# Infinity_Mirror_002.net
KiCad netlist of a schematic drawn in EAGLE
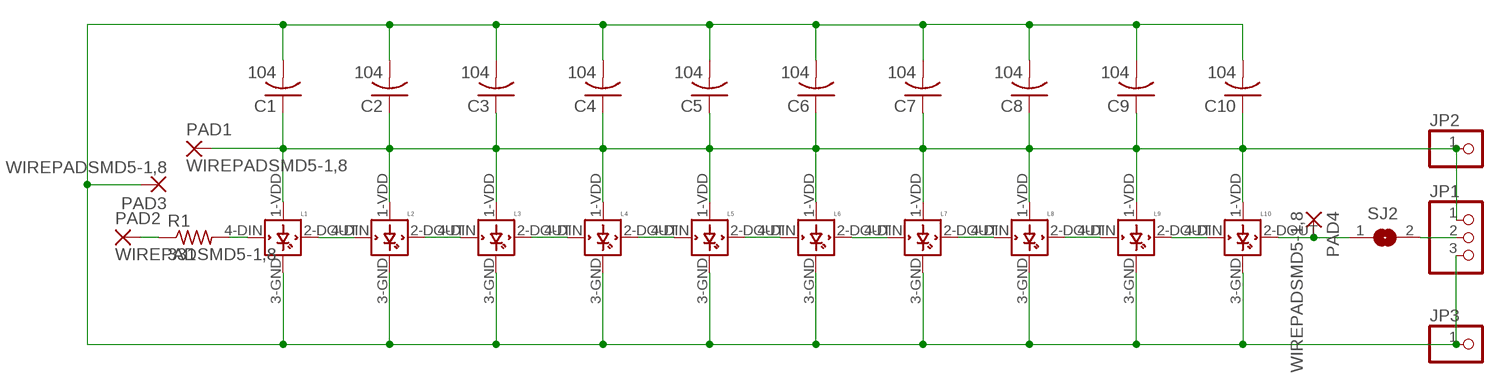
[diagram p0: schematic, sheet 1]

(export (version "E")
  (design (tool "Eeschema 10.0.6"))
  (components
    (comp (ref "C1")
      (value "104")
      (footprint "eagle-import:C1206")
      (libsource (lib "eagle-import") (part "C-USC1206"))
    )
    (comp (ref "C2")
      (value "104")
      (footprint "eagle-import:C1206")
      (libsource (lib "eagle-import") (part "C-USC1206"))
    )
    (comp (ref "C3")
      (value "104")
      (footprint "eagle-import:C1206")
      (libsource (lib "eagle-import") (part "C-USC1206"))
    )
    (comp (ref "C4")
      (value "104")
      (footprint "eagle-import:C1206")
      (libsource (lib "eagle-import") (part "C-USC1206"))
    )
    (comp (ref "C5")
      (value "104")
      (footprint "eagle-import:C1206")
      (libsource (lib "eagle-import") (part "C-USC1206"))
    )
    (comp (ref "C6")
      (value "104")
      (footprint "eagle-import:C1206")
      (libsource (lib "eagle-import") (part "C-USC1206"))
    )
    (comp (ref "C7")
      (value "104")
      (footprint "eagle-import:C1206")
      (libsource (lib "eagle-import") (part "C-USC1206"))
    )
    (comp (ref "C8")
      (value "104")
      (footprint "eagle-import:C1206")
      (libsource (lib "eagle-import") (part "C-USC1206"))
    )
    (comp (ref "C9")
      (value "104")
      (footprint "eagle-import:C1206")
      (libsource (lib "eagle-import") (part "C-USC1206"))
    )
    (comp (ref "C10")
      (value "104")
      (footprint "eagle-import:C1206")
      (libsource (lib "eagle-import") (part "C-USC1206"))
    )
    (comp (ref "JP1")
      (value "PINHD-1X3CB")
      (footprint "eagle-import:1X03-CLEANBIG")
      (libsource (lib "eagle-import") (part "PINHD-1X3CB"))
    )
    (comp (ref "JP2")
      (value "PINHD-1X1CB")
      (footprint "eagle-import:1X01-CLEANBIG")
      (libsource (lib "eagle-import") (part "PINHD-1X1CB"))
    )
    (comp (ref "JP3")
      (value "PINHD-1X1CB")
      (footprint "eagle-import:1X01-CLEANBIG")
      (libsource (lib "eagle-import") (part "PINHD-1X1CB"))
    )
    (comp (ref "L1")
      (value "WS2812B")
      (footprint "eagle-import:WS2812B")
      (libsource (lib "eagle-import") (part "WS2812B"))
    )
    (comp (ref "L2")
      (value "WS2812B")
      (footprint "eagle-import:WS2812B")
      (libsource (lib "eagle-import") (part "WS2812B"))
    )
    (comp (ref "L3")
      (value "WS2812B")
      (footprint "eagle-import:WS2812B")
      (libsource (lib "eagle-import") (part "WS2812B"))
    )
    (comp (ref "L4")
      (value "WS2812B")
      (footprint "eagle-import:WS2812B")
      (libsource (lib "eagle-import") (part "WS2812B"))
    )
    (comp (ref "L5")
      (value "WS2812B")
      (footprint "eagle-import:WS2812B")
      (libsource (lib "eagle-import") (part "WS2812B"))
    )
    (comp (ref "L6")
      (value "WS2812B")
      (footprint "eagle-import:WS2812B")
      (libsource (lib "eagle-import") (part "WS2812B"))
    )
    (comp (ref "L7")
      (value "WS2812B")
      (footprint "eagle-import:WS2812B")
      (libsource (lib "eagle-import") (part "WS2812B"))
    )
    (comp (ref "L8")
      (value "WS2812B")
      (footprint "eagle-import:WS2812B")
      (libsource (lib "eagle-import") (part "WS2812B"))
    )
    (comp (ref "L9")
      (value "WS2812B")
      (footprint "eagle-import:WS2812B")
      (libsource (lib "eagle-import") (part "WS2812B"))
    )
    (comp (ref "L10")
      (value "WS2812B")
      (footprint "eagle-import:WS2812B")
      (libsource (lib "eagle-import") (part "WS2812B"))
    )
    (comp (ref "PAD1")
      (value "WIREPADSMD5-1,8")
      (footprint "eagle-import:5-1,8")
      (libsource (lib "eagle-import") (part "WIREPADSMD5-1,8"))
    )
    (comp (ref "PAD2")
      (value "WIREPADSMD5-1,8")
      (footprint "eagle-import:5-1,8")
      (libsource (lib "eagle-import") (part "WIREPADSMD5-1,8"))
    )
    (comp (ref "PAD3")
      (value "WIREPADSMD5-1,8")
      (footprint "eagle-import:5-1,8")
      (libsource (lib "eagle-import") (part "WIREPADSMD5-1,8"))
    )
    (comp (ref "PAD4")
      (value "WIREPADSMD5-1,8")
      (footprint "eagle-import:5-1,8")
      (libsource (lib "eagle-import") (part "WIREPADSMD5-1,8"))
    )
    (comp (ref "R1")
      (value "331")
      (footprint "eagle-import:R1206")
      (libsource (lib "eagle-import") (part "R-US_R1206"))
    )
    (comp (ref "SJ2") (value "SJ") (footprint "eagle-import:SJ") (libsource (lib "eagle-import") (part "SJ")))
  )
  (nets
    (net (code "1") (name "Net-(JP1-Pad2)") (class "Default")
      (node (ref "JP1") (pin "2") (pinfunction "2_2") (pintype "passive"))
      (node (ref "SJ2") (pin "2") (pinfunction "2_2") (pintype "passive"))
    )
    (net (code "2") (name "Net-(L1-DIN)") (class "Default")
      (node (ref "L1") (pin "4-DIN") (pinfunction "DIN_4-DIN") (pintype "input"))
      (node (ref "R1") (pin "2") (pinfunction "2_2") (pintype "passive"))
    )
    (net (code "3") (name "Net-(L1-DOUT)") (class "Default")
      (node (ref "L1") (pin "2-DOUT") (pinfunction "DOUT_2-DOUT") (pintype "output"))
      (node (ref "L2") (pin "4-DIN") (pinfunction "DIN_4-DIN") (pintype "input"))
    )
    (net (code "4") (name "Net-(L1-GND)") (class "Default")
      (node (ref "C1") (pin "2") (pinfunction "2_2") (pintype "passive"))
      (node (ref "C10") (pin "2") (pinfunction "2_2") (pintype "passive"))
      (node (ref "C2") (pin "2") (pinfunction "2_2") (pintype "passive"))
      (node (ref "C3") (pin "2") (pinfunction "2_2") (pintype "passive"))
      (node (ref "C4") (pin "2") (pinfunction "2_2") (pintype "passive"))
      (node (ref "C5") (pin "2") (pinfunction "2_2") (pintype "passive"))
      (node (ref "C6") (pin "2") (pinfunction "2_2") (pintype "passive"))
      (node (ref "C7") (pin "2") (pinfunction "2_2") (pintype "passive"))
      (node (ref "C8") (pin "2") (pinfunction "2_2") (pintype "passive"))
      (node (ref "C9") (pin "2") (pinfunction "2_2") (pintype "passive"))
      (node (ref "JP1") (pin "3") (pinfunction "3_3") (pintype "passive"))
      (node (ref "JP3") (pin "1") (pinfunction "1_1") (pintype "passive"))
      (node (ref "L1") (pin "3-GND") (pinfunction "GND_3-GND") (pintype "bidirectional"))
      (node (ref "L10") (pin "3-GND") (pinfunction "GND_3-GND") (pintype "bidirectional"))
      (node (ref "L2") (pin "3-GND") (pinfunction "GND_3-GND") (pintype "bidirectional"))
      (node (ref "L3") (pin "3-GND") (pinfunction "GND_3-GND") (pintype "bidirectional"))
      (node (ref "L4") (pin "3-GND") (pinfunction "GND_3-GND") (pintype "bidirectional"))
      (node (ref "L5") (pin "3-GND") (pinfunction "GND_3-GND") (pintype "bidirectional"))
      (node (ref "L6") (pin "3-GND") (pinfunction "GND_3-GND") (pintype "bidirectional"))
      (node (ref "L7") (pin "3-GND") (pinfunction "GND_3-GND") (pintype "bidirectional"))
      (node (ref "L8") (pin "3-GND") (pinfunction "GND_3-GND") (pintype "bidirectional"))
      (node (ref "L9") (pin "3-GND") (pinfunction "GND_3-GND") (pintype "bidirectional"))
      (node (ref "PAD3") (pin "1") (pinfunction "P_1") (pintype "passive"))
    )
    (net (code "5") (name "Net-(L1-VDD)") (class "Default")
      (node (ref "C1") (pin "1") (pinfunction "1_1") (pintype "passive"))
      (node (ref "C10") (pin "1") (pinfunction "1_1") (pintype "passive"))
      (node (ref "C2") (pin "1") (pinfunction "1_1") (pintype "passive"))
      (node (ref "C3") (pin "1") (pinfunction "1_1") (pintype "passive"))
      (node (ref "C4") (pin "1") (pinfunction "1_1") (pintype "passive"))
      (node (ref "C5") (pin "1") (pinfunction "1_1") (pintype "passive"))
      (node (ref "C6") (pin "1") (pinfunction "1_1") (pintype "passive"))
      (node (ref "C7") (pin "1") (pinfunction "1_1") (pintype "passive"))
      (node (ref "C8") (pin "1") (pinfunction "1_1") (pintype "passive"))
      (node (ref "C9") (pin "1") (pinfunction "1_1") (pintype "passive"))
      (node (ref "JP1") (pin "1") (pinfunction "1_1") (pintype "passive"))
      (node (ref "JP2") (pin "1") (pinfunction "1_1") (pintype "passive"))
      (node (ref "L1") (pin "1-VDD") (pinfunction "VDD_1-VDD") (pintype "bidirectional"))
      (node (ref "L10") (pin "1-VDD") (pinfunction "VDD_1-VDD") (pintype "bidirectional"))
      (node (ref "L2") (pin "1-VDD") (pinfunction "VDD_1-VDD") (pintype "bidirectional"))
      (node (ref "L3") (pin "1-VDD") (pinfunction "VDD_1-VDD") (pintype "bidirectional"))
      (node (ref "L4") (pin "1-VDD") (pinfunction "VDD_1-VDD") (pintype "bidirectional"))
      (node (ref "L5") (pin "1-VDD") (pinfunction "VDD_1-VDD") (pintype "bidirectional"))
      (node (ref "L6") (pin "1-VDD") (pinfunction "VDD_1-VDD") (pintype "bidirectional"))
      (node (ref "L7") (pin "1-VDD") (pinfunction "VDD_1-VDD") (pintype "bidirectional"))
      (node (ref "L8") (pin "1-VDD") (pinfunction "VDD_1-VDD") (pintype "bidirectional"))
      (node (ref "L9") (pin "1-VDD") (pinfunction "VDD_1-VDD") (pintype "bidirectional"))
      (node (ref "PAD1") (pin "1") (pinfunction "P_1") (pintype "passive"))
    )
    (net (code "6") (name "Net-(L2-DOUT)") (class "Default")
      (node (ref "L2") (pin "2-DOUT") (pinfunction "DOUT_2-DOUT") (pintype "output"))
      (node (ref "L3") (pin "4-DIN") (pinfunction "DIN_4-DIN") (pintype "input"))
    )
    (net (code "7") (name "Net-(L3-DOUT)") (class "Default")
      (node (ref "L3") (pin "2-DOUT") (pinfunction "DOUT_2-DOUT") (pintype "output"))
      (node (ref "L4") (pin "4-DIN") (pinfunction "DIN_4-DIN") (pintype "input"))
    )
    (net (code "8") (name "Net-(L4-DOUT)") (class "Default")
      (node (ref "L4") (pin "2-DOUT") (pinfunction "DOUT_2-DOUT") (pintype "output"))
      (node (ref "L5") (pin "4-DIN") (pinfunction "DIN_4-DIN") (pintype "input"))
    )
    (net (code "9") (name "Net-(L5-DOUT)") (class "Default")
      (node (ref "L5") (pin "2-DOUT") (pinfunction "DOUT_2-DOUT") (pintype "output"))
      (node (ref "L6") (pin "4-DIN") (pinfunction "DIN_4-DIN") (pintype "input"))
    )
    (net (code "10") (name "Net-(L6-DOUT)") (class "Default")
      (node (ref "L6") (pin "2-DOUT") (pinfunction "DOUT_2-DOUT") (pintype "output"))
      (node (ref "L7") (pin "4-DIN") (pinfunction "DIN_4-DIN") (pintype "input"))
    )
    (net (code "11") (name "Net-(L7-DOUT)") (class "Default")
      (node (ref "L7") (pin "2-DOUT") (pinfunction "DOUT_2-DOUT") (pintype "output"))
      (node (ref "L8") (pin "4-DIN") (pinfunction "DIN_4-DIN") (pintype "input"))
    )
    (net (code "12") (name "Net-(L8-DOUT)") (class "Default")
      (node (ref "L8") (pin "2-DOUT") (pinfunction "DOUT_2-DOUT") (pintype "output"))
      (node (ref "L9") (pin "4-DIN") (pinfunction "DIN_4-DIN") (pintype "input"))
    )
    (net (code "13") (name "Net-(L10-DIN)") (class "Default")
      (node (ref "L10") (pin "4-DIN") (pinfunction "DIN_4-DIN") (pintype "input"))
      (node (ref "L9") (pin "2-DOUT") (pinfunction "DOUT_2-DOUT") (pintype "output"))
    )
    (net (code "14") (name "Net-(L10-DOUT)") (class "Default")
      (node (ref "L10") (pin "2-DOUT") (pinfunction "DOUT_2-DOUT") (pintype "output"))
      (node (ref "PAD4") (pin "1") (pinfunction "P_1") (pintype "passive"))
      (node (ref "SJ2") (pin "1") (pinfunction "1_1") (pintype "passive"))
    )
    (net (code "15") (name "Net-(PAD2-P)") (class "Default")
      (node (ref "PAD2") (pin "1") (pinfunction "P_1") (pintype "passive"))
      (node (ref "R1") (pin "1") (pinfunction "1_1") (pintype "passive"))
    )
  )
)
